# A7_FUNCTION2.net
KiCad netlist of a schematic drawn in Altium Designer
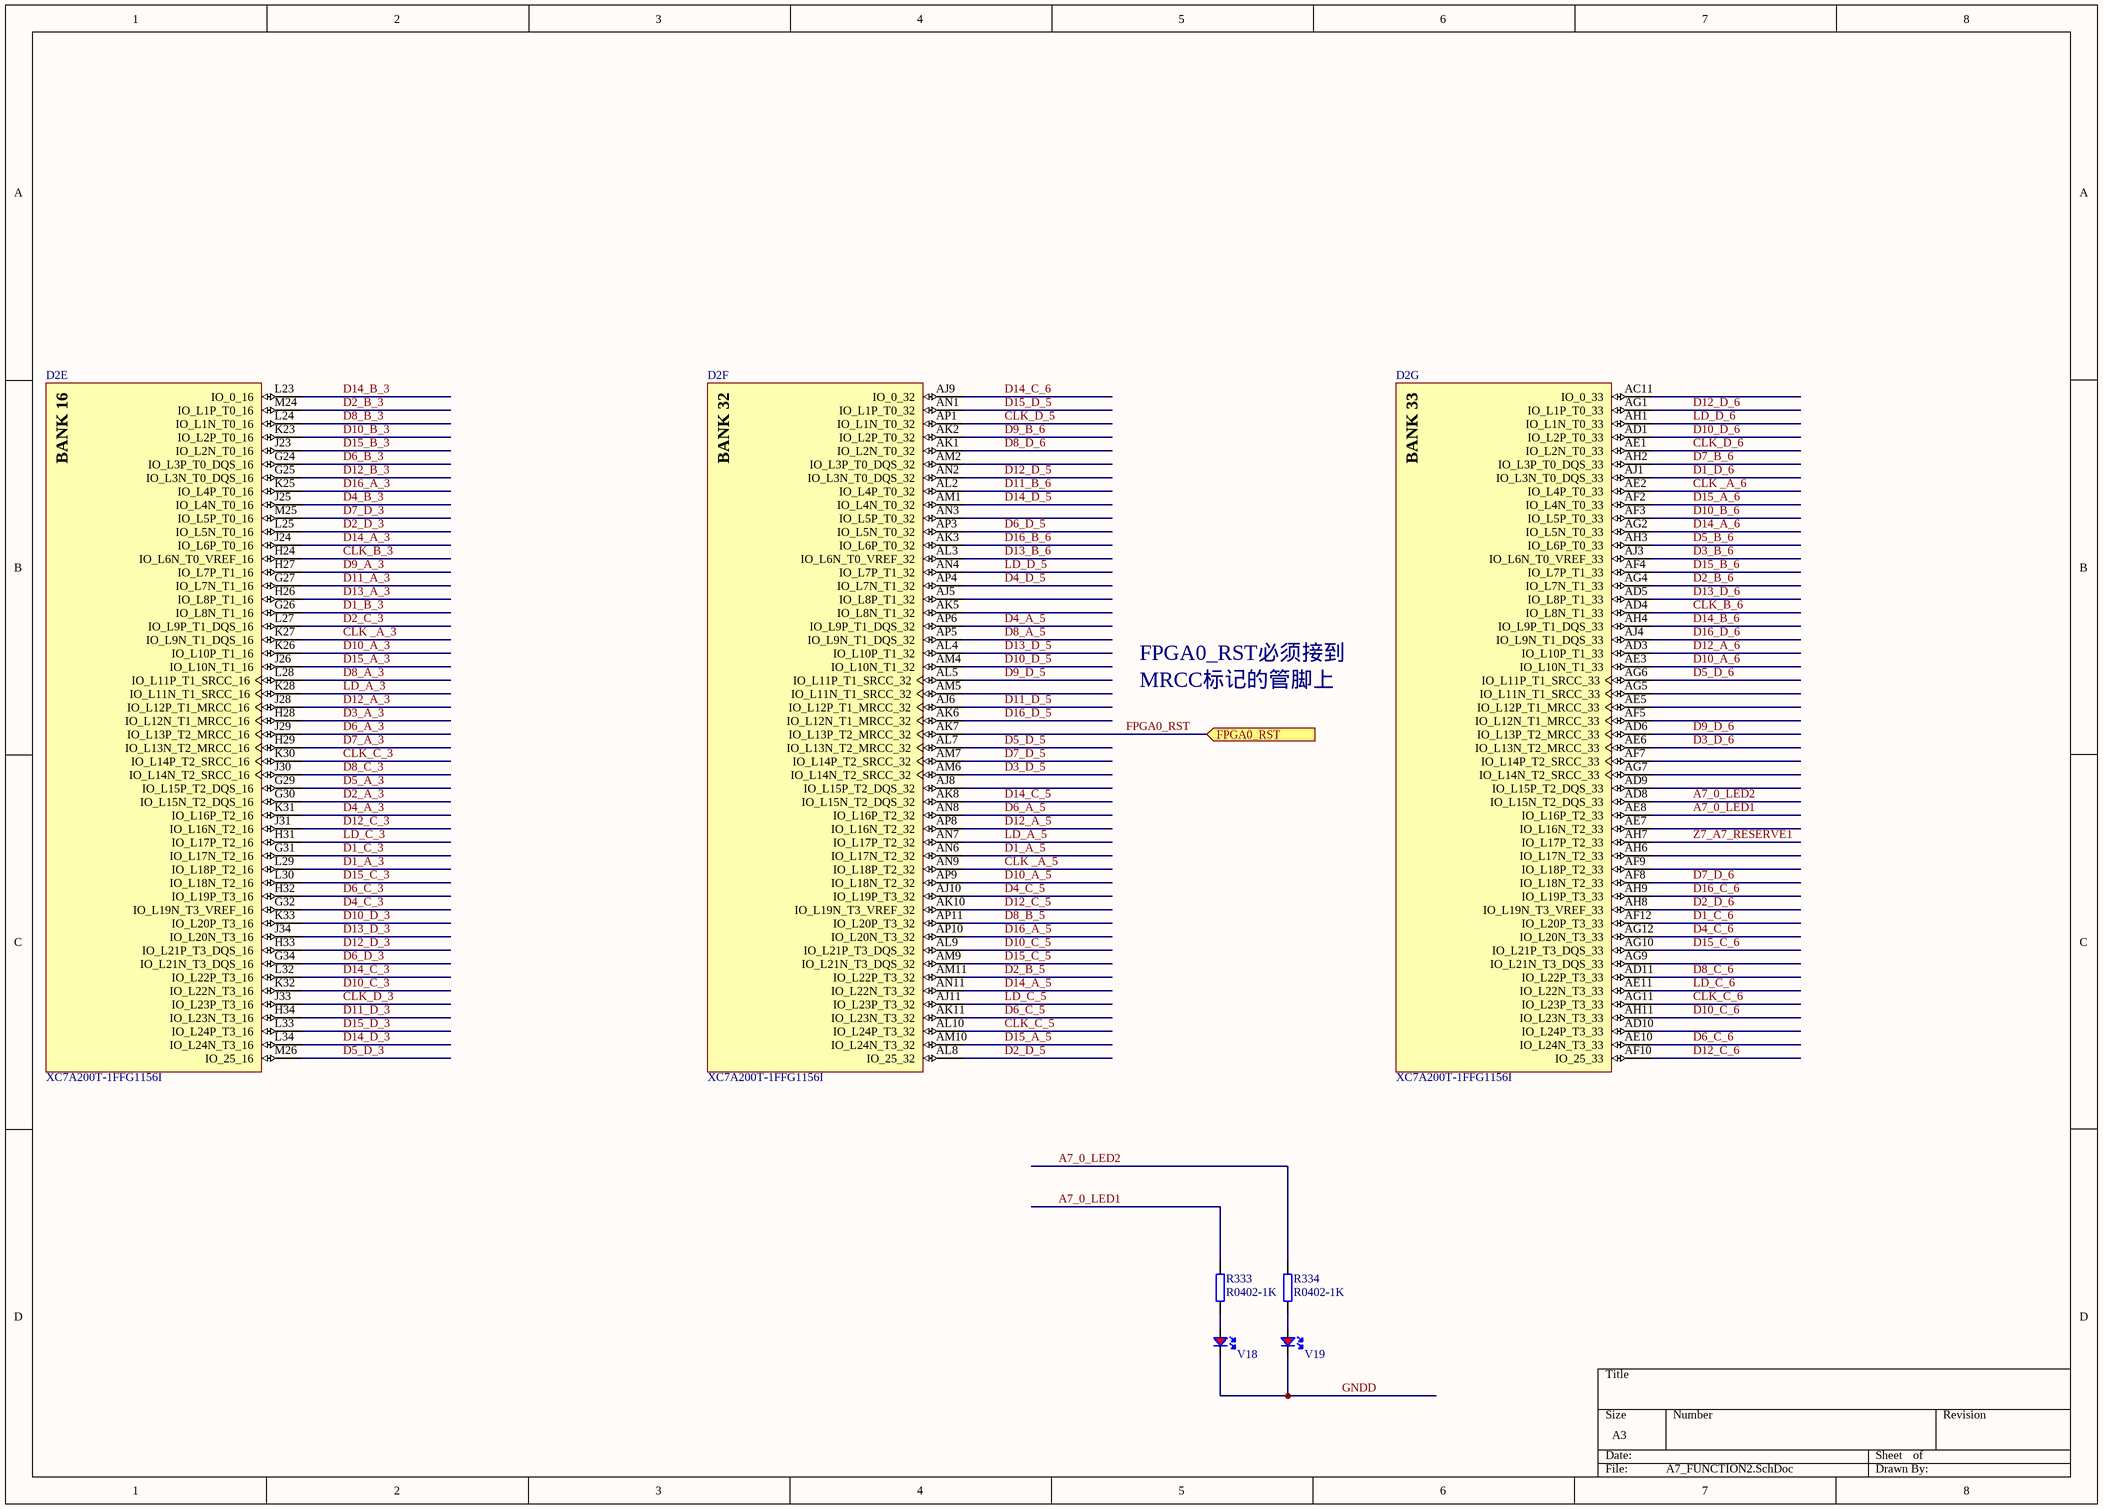
[diagram p0: A7_FUNCTION2.SchDoc]

(export (version "E")
  (design (tool "Eeschema 10.0.6"))
  (components
    (comp (ref "D2")
      (value "XC7A200T-1FFG1156I")
      (footprint "FFG1156")
      (description "Artix-7 FPGA, 500 User I/Os, 16 GTP, 1156-Ball BGA, Speed Grade 1, Industrial Grade, Pb-Free")
      (fields (field (name "GENERIC PART NUMBER") "XC7A200T") (field (name "MANUFACTURER") "Xilinx"))
      (libsource (lib "Xilinx Artix-7") (part "XC7A200T-1FFG1156I"))
    )
    (comp (ref "R333")
      (value "R0402-1K")
      (footprint "R0402")
      (fields (field (name "SCHEMATIC_PART") "RES") (field (name "MANUFACTURER") "SAMSUNG"))
      (libsource (lib "Database_Libs1") (part "RES"))
    )
    (comp (ref "R334")
      (value "R0402-1K")
      (footprint "R0402")
      (fields (field (name "SCHEMATIC_PART") "RES") (field (name "MANUFACTURER") "SAMSUNG"))
      (libsource (lib "Database_Libs1") (part "RES"))
    )
    (comp (ref "V18")
      (value "LED-R0603")
      (footprint "LED-R0603")
      (description "表贴发光二极管, 0603封装, 体积1.6x0.8mm, 红色, 高度0.8mm")
      (fields (field (name "SCHEMATIC_PART") "LED-R"))
      (libsource (lib "Database_Libs1") (part "LED-R"))
    )
    (comp (ref "V19")
      (value "LED-R0603")
      (footprint "LED-R0603")
      (description "表贴发光二极管, 0603封装, 体积1.6x0.8mm, 红色, 高度0.8mm")
      (fields (field (name "SCHEMATIC_PART") "LED-R"))
      (libsource (lib "Database_Libs1") (part "LED-R"))
    )
  )
  (nets
    (net (code "1") (name "/A7_0_LED1") (class "Default")
      (node (ref "D2") (pin "AE8") (pinfunction "IO_L16P_T2_33_AE8") (pintype "bidirectional"))
      (node (ref "R333") (pin "2") (pintype "passive"))
    )
    (net (code "2") (name "/A7_0_LED2") (class "Default")
      (node (ref "D2") (pin "AD8") (pinfunction "IO_L15N_T2_DQS_33_AD8") (pintype "bidirectional"))
      (node (ref "R334") (pin "2") (pintype "passive"))
    )
    (net (code "3") (name "/CLK _A_3") (class "Default")
      (node (ref "D2") (pin "K27") (pinfunction "IO_L9N_T1_DQS_16_K27") (pintype "bidirectional"))
    )
    (net (code "4") (name "/CLK _A_5") (class "Default")
      (node (ref "D2") (pin "AN9") (pinfunction "IO_L18P_T2_32_AN9") (pintype "bidirectional"))
    )
    (net (code "5") (name "/CLK _A_6") (class "Default")
      (node (ref "D2") (pin "AE2") (pinfunction "IO_L4P_T0_33_AE2") (pintype "bidirectional"))
    )
    (net (code "6") (name "/CLK_B_3") (class "Default")
      (node (ref "D2") (pin "H24") (pinfunction "IO_L6N_T0_VREF_16_H24") (pintype "bidirectional"))
    )
    (net (code "7") (name "/CLK_B_6") (class "Default")
      (node (ref "D2") (pin "AD4") (pinfunction "IO_L8N_T1_33_AD4") (pintype "bidirectional"))
    )
    (net (code "8") (name "/CLK_C_3") (class "Default")
      (node (ref "D2") (pin "K30") (pinfunction "IO_L14P_T2_SRCC_16_K30") (pintype "bidirectional"))
    )
    (net (code "9") (name "/CLK_C_5") (class "Default")
      (node (ref "D2") (pin "AL10") (pinfunction "IO_L24P_T3_32_AL10") (pintype "bidirectional"))
    )
    (net (code "10") (name "/CLK_C_6") (class "Default")
      (node (ref "D2") (pin "AG11") (pinfunction "IO_L23P_T3_33_AG11") (pintype "bidirectional"))
    )
    (net (code "11") (name "/CLK_D_3") (class "Default")
      (node (ref "D2") (pin "J33") (pinfunction "IO_L23P_T3_16_J33") (pintype "bidirectional"))
    )
    (net (code "12") (name "/CLK_D_5") (class "Default")
      (node (ref "D2") (pin "AP1") (pinfunction "IO_L1N_T0_32_AP1") (pintype "bidirectional"))
    )
    (net (code "13") (name "/CLK_D_6") (class "Default")
      (node (ref "D2") (pin "AE1") (pinfunction "IO_L2N_T0_33_AE1") (pintype "bidirectional"))
    )
    (net (code "14") (name "/D1_A_3") (class "Default")
      (node (ref "D2") (pin "L29") (pinfunction "IO_L18P_T2_16_L29") (pintype "bidirectional"))
    )
    (net (code "15") (name "/D1_A_5") (class "Default")
      (node (ref "D2") (pin "AN6") (pinfunction "IO_L17N_T2_32_AN6") (pintype "bidirectional"))
    )
    (net (code "16") (name "/D1_B_3") (class "Default")
      (node (ref "D2") (pin "G26") (pinfunction "IO_L8N_T1_16_G26") (pintype "bidirectional"))
    )
    (net (code "17") (name "/D1_C_3") (class "Default")
      (node (ref "D2") (pin "G31") (pinfunction "IO_L17N_T2_16_G31") (pintype "bidirectional"))
    )
    (net (code "18") (name "/D1_C_6") (class "Default")
      (node (ref "D2") (pin "AF12") (pinfunction "IO_L20P_T3_33_AF12") (pintype "bidirectional"))
    )
    (net (code "19") (name "/D1_D_6") (class "Default")
      (node (ref "D2") (pin "AJ1") (pinfunction "IO_L3N_T0_DQS_33_AJ1") (pintype "bidirectional"))
    )
    (net (code "20") (name "/D2_A_3") (class "Default")
      (node (ref "D2") (pin "G30") (pinfunction "IO_L15N_T2_DQS_16_G30") (pintype "bidirectional"))
    )
    (net (code "21") (name "/D2_B_3") (class "Default")
      (node (ref "D2") (pin "M24") (pinfunction "IO_L1P_T0_16_M24") (pintype "bidirectional"))
    )
    (net (code "22") (name "/D2_B_5") (class "Default")
      (node (ref "D2") (pin "AM11") (pinfunction "IO_L22P_T3_32_AM11") (pintype "bidirectional"))
    )
    (net (code "23") (name "/D2_B_6") (class "Default")
      (node (ref "D2") (pin "AG4") (pinfunction "IO_L7N_T1_33_AG4") (pintype "bidirectional"))
    )
    (net (code "24") (name "/D2_C_3") (class "Default")
      (node (ref "D2") (pin "L27") (pinfunction "IO_L9P_T1_DQS_16_L27") (pintype "bidirectional"))
    )
    (net (code "25") (name "/D2_D_3") (class "Default")
      (node (ref "D2") (pin "L25") (pinfunction "IO_L5N_T0_16_L25") (pintype "bidirectional"))
    )
    (net (code "26") (name "/D2_D_5") (class "Default")
      (node (ref "D2") (pin "AL8") (pinfunction "IO_25_32_AL8") (pintype "bidirectional"))
    )
    (net (code "27") (name "/D2_D_6") (class "Default")
      (node (ref "D2") (pin "AH8") (pinfunction "IO_L19N_T3_VREF_33_AH8") (pintype "bidirectional"))
    )
    (net (code "28") (name "/D3_A_3") (class "Default")
      (node (ref "D2") (pin "H28") (pinfunction "IO_L12N_T1_MRCC_16_H28") (pintype "bidirectional"))
    )
    (net (code "29") (name "/D3_B_6") (class "Default")
      (node (ref "D2") (pin "AJ3") (pinfunction "IO_L6N_T0_VREF_33_AJ3") (pintype "bidirectional"))
    )
    (net (code "30") (name "/D3_D_5") (class "Default")
      (node (ref "D2") (pin "AM6") (pinfunction "IO_L14N_T2_SRCC_32_AM6") (pintype "bidirectional"))
    )
    (net (code "31") (name "/D3_D_6") (class "Default")
      (node (ref "D2") (pin "AE6") (pinfunction "IO_L13N_T2_MRCC_33_AE6") (pintype "bidirectional"))
    )
    (net (code "32") (name "/D4_A_3") (class "Default")
      (node (ref "D2") (pin "K31") (pinfunction "IO_L16P_T2_16_K31") (pintype "bidirectional"))
    )
    (net (code "33") (name "/D4_A_5") (class "Default")
      (node (ref "D2") (pin "AP6") (pinfunction "IO_L9P_T1_DQS_32_AP6") (pintype "bidirectional"))
    )
    (net (code "34") (name "/D4_B_3") (class "Default")
      (node (ref "D2") (pin "J25") (pinfunction "IO_L4N_T0_16_J25") (pintype "bidirectional"))
    )
    (net (code "35") (name "/D4_C_3") (class "Default")
      (node (ref "D2") (pin "G32") (pinfunction "IO_L19N_T3_VREF_16_G32") (pintype "bidirectional"))
    )
    (net (code "36") (name "/D4_C_5") (class "Default")
      (node (ref "D2") (pin "AJ10") (pinfunction "IO_L19P_T3_32_AJ10") (pintype "bidirectional"))
    )
    (net (code "37") (name "/D4_C_6") (class "Default")
      (node (ref "D2") (pin "AG12") (pinfunction "IO_L20N_T3_33_AG12") (pintype "bidirectional"))
    )
    (net (code "38") (name "/D4_D_5") (class "Default")
      (node (ref "D2") (pin "AP4") (pinfunction "IO_L7N_T1_32_AP4") (pintype "bidirectional"))
    )
    (net (code "39") (name "/D5_A_3") (class "Default")
      (node (ref "D2") (pin "G29") (pinfunction "IO_L15P_T2_DQS_16_G29") (pintype "bidirectional"))
    )
    (net (code "40") (name "/D5_B_6") (class "Default")
      (node (ref "D2") (pin "AH3") (pinfunction "IO_L6P_T0_33_AH3") (pintype "bidirectional"))
    )
    (net (code "41") (name "/D5_D_3") (class "Default")
      (node (ref "D2") (pin "M26") (pinfunction "IO_25_16_M26") (pintype "bidirectional"))
    )
    (net (code "42") (name "/D5_D_5") (class "Default")
      (node (ref "D2") (pin "AL7") (pinfunction "IO_L13N_T2_MRCC_32_AL7") (pintype "bidirectional"))
    )
    (net (code "43") (name "/D5_D_6") (class "Default")
      (node (ref "D2") (pin "AG6") (pinfunction "IO_L11P_T1_SRCC_33_AG6") (pintype "bidirectional"))
    )
    (net (code "44") (name "/D6_A_3") (class "Default")
      (node (ref "D2") (pin "J29") (pinfunction "IO_L13P_T2_MRCC_16_J29") (pintype "bidirectional"))
    )
    (net (code "45") (name "/D6_A_5") (class "Default")
      (node (ref "D2") (pin "AN8") (pinfunction "IO_L16P_T2_32_AN8") (pintype "bidirectional"))
    )
    (net (code "46") (name "/D6_B_3") (class "Default")
      (node (ref "D2") (pin "G24") (pinfunction "IO_L3P_T0_DQS_16_G24") (pintype "bidirectional"))
    )
    (net (code "47") (name "/D6_C_3") (class "Default")
      (node (ref "D2") (pin "H32") (pinfunction "IO_L19P_T3_16_H32") (pintype "bidirectional"))
    )
    (net (code "48") (name "/D6_C_5") (class "Default")
      (node (ref "D2") (pin "AK11") (pinfunction "IO_L23N_T3_32_AK11") (pintype "bidirectional"))
    )
    (net (code "49") (name "/D6_C_6") (class "Default")
      (node (ref "D2") (pin "AE10") (pinfunction "IO_L24N_T3_33_AE10") (pintype "bidirectional"))
    )
    (net (code "50") (name "/D6_D_3") (class "Default")
      (node (ref "D2") (pin "G34") (pinfunction "IO_L21N_T3_DQS_16_G34") (pintype "bidirectional"))
    )
    (net (code "51") (name "/D6_D_5") (class "Default")
      (node (ref "D2") (pin "AP3") (pinfunction "IO_L5N_T0_32_AP3") (pintype "bidirectional"))
    )
    (net (code "52") (name "/D7_A_3") (class "Default")
      (node (ref "D2") (pin "H29") (pinfunction "IO_L13N_T2_MRCC_16_H29") (pintype "bidirectional"))
    )
    (net (code "53") (name "/D7_B_6") (class "Default")
      (node (ref "D2") (pin "AH2") (pinfunction "IO_L3P_T0_DQS_33_AH2") (pintype "bidirectional"))
    )
    (net (code "54") (name "/D7_D_3") (class "Default")
      (node (ref "D2") (pin "M25") (pinfunction "IO_L5P_T0_16_M25") (pintype "bidirectional"))
    )
    (net (code "55") (name "/D7_D_5") (class "Default")
      (node (ref "D2") (pin "AM7") (pinfunction "IO_L14P_T2_SRCC_32_AM7") (pintype "bidirectional"))
    )
    (net (code "56") (name "/D7_D_6") (class "Default")
      (node (ref "D2") (pin "AF8") (pinfunction "IO_L18N_T2_33_AF8") (pintype "bidirectional"))
    )
    (net (code "57") (name "/D8_A_3") (class "Default")
      (node (ref "D2") (pin "L28") (pinfunction "IO_L11P_T1_SRCC_16_L28") (pintype "bidirectional"))
    )
    (net (code "58") (name "/D8_A_5") (class "Default")
      (node (ref "D2") (pin "AP5") (pinfunction "IO_L9N_T1_DQS_32_AP5") (pintype "bidirectional"))
    )
    (net (code "59") (name "/D8_B_3") (class "Default")
      (node (ref "D2") (pin "L24") (pinfunction "IO_L1N_T0_16_L24") (pintype "bidirectional"))
    )
    (net (code "60") (name "/D8_B_5") (class "Default")
      (node (ref "D2") (pin "AP11") (pinfunction "IO_L20P_T3_32_AP11") (pintype "bidirectional"))
    )
    (net (code "61") (name "/D8_C_3") (class "Default")
      (node (ref "D2") (pin "J30") (pinfunction "IO_L14N_T2_SRCC_16_J30") (pintype "bidirectional"))
    )
    (net (code "62") (name "/D8_C_6") (class "Default")
      (node (ref "D2") (pin "AD11") (pinfunction "IO_L22P_T3_33_AD11") (pintype "bidirectional"))
    )
    (net (code "63") (name "/D8_D_6") (class "Default")
      (node (ref "D2") (pin "AK1") (pinfunction "IO_L2N_T0_32_AK1") (pintype "bidirectional"))
    )
    (net (code "64") (name "/D9_A_3") (class "Default")
      (node (ref "D2") (pin "H27") (pinfunction "IO_L7P_T1_16_H27") (pintype "bidirectional"))
    )
    (net (code "65") (name "/D9_B_6") (class "Default")
      (node (ref "D2") (pin "AK2") (pinfunction "IO_L2P_T0_32_AK2") (pintype "bidirectional"))
    )
    (net (code "66") (name "/D9_D_5") (class "Default")
      (node (ref "D2") (pin "AL5") (pinfunction "IO_L11P_T1_SRCC_32_AL5") (pintype "bidirectional"))
    )
    (net (code "67") (name "/D9_D_6") (class "Default")
      (node (ref "D2") (pin "AD6") (pinfunction "IO_L13P_T2_MRCC_33_AD6") (pintype "bidirectional"))
    )
    (net (code "68") (name "/D10_A_3") (class "Default")
      (node (ref "D2") (pin "K26") (pinfunction "IO_L10P_T1_16_K26") (pintype "bidirectional"))
    )
    (net (code "69") (name "/D10_A_5") (class "Default")
      (node (ref "D2") (pin "AP9") (pinfunction "IO_L18N_T2_32_AP9") (pintype "bidirectional"))
    )
    (net (code "70") (name "/D10_A_6") (class "Default")
      (node (ref "D2") (pin "AE3") (pinfunction "IO_L10N_T1_33_AE3") (pintype "bidirectional"))
    )
    (net (code "71") (name "/D10_B_3") (class "Default")
      (node (ref "D2") (pin "K23") (pinfunction "IO_L2P_T0_16_K23") (pintype "bidirectional"))
    )
    (net (code "72") (name "/D10_B_6") (class "Default")
      (node (ref "D2") (pin "AF3") (pinfunction "IO_L5P_T0_33_AF3") (pintype "bidirectional"))
    )
    (net (code "73") (name "/D10_C_3") (class "Default")
      (node (ref "D2") (pin "K32") (pinfunction "IO_L22N_T3_16_K32") (pintype "bidirectional"))
    )
    (net (code "74") (name "/D10_C_5") (class "Default")
      (node (ref "D2") (pin "AL9") (pinfunction "IO_L21P_T3_DQS_32_AL9") (pintype "bidirectional"))
    )
    (net (code "75") (name "/D10_C_6") (class "Default")
      (node (ref "D2") (pin "AH11") (pinfunction "IO_L23N_T3_33_AH11") (pintype "bidirectional"))
    )
    (net (code "76") (name "/D10_D_3") (class "Default")
      (node (ref "D2") (pin "K33") (pinfunction "IO_L20P_T3_16_K33") (pintype "bidirectional"))
    )
    (net (code "77") (name "/D10_D_5") (class "Default")
      (node (ref "D2") (pin "AM4") (pinfunction "IO_L10N_T1_32_AM4") (pintype "bidirectional"))
    )
    (net (code "78") (name "/D10_D_6") (class "Default")
      (node (ref "D2") (pin "AD1") (pinfunction "IO_L2P_T0_33_AD1") (pintype "bidirectional"))
    )
    (net (code "79") (name "/D11_A_3") (class "Default")
      (node (ref "D2") (pin "G27") (pinfunction "IO_L7N_T1_16_G27") (pintype "bidirectional"))
    )
    (net (code "80") (name "/D11_B_6") (class "Default")
      (node (ref "D2") (pin "AL2") (pinfunction "IO_L4P_T0_32_AL2") (pintype "bidirectional"))
    )
    (net (code "81") (name "/D11_D_3") (class "Default")
      (node (ref "D2") (pin "H34") (pinfunction "IO_L23N_T3_16_H34") (pintype "bidirectional"))
    )
    (net (code "82") (name "/D11_D_5") (class "Default")
      (node (ref "D2") (pin "AJ6") (pinfunction "IO_L12P_T1_MRCC_32_AJ6") (pintype "bidirectional"))
    )
    (net (code "83") (name "/D12_A_3") (class "Default")
      (node (ref "D2") (pin "J28") (pinfunction "IO_L12P_T1_MRCC_16_J28") (pintype "bidirectional"))
    )
    (net (code "84") (name "/D12_A_5") (class "Default")
      (node (ref "D2") (pin "AP8") (pinfunction "IO_L16N_T2_32_AP8") (pintype "bidirectional"))
    )
    (net (code "85") (name "/D12_A_6") (class "Default")
      (node (ref "D2") (pin "AD3") (pinfunction "IO_L10P_T1_33_AD3") (pintype "bidirectional"))
    )
    (net (code "86") (name "/D12_B_3") (class "Default")
      (node (ref "D2") (pin "G25") (pinfunction "IO_L3N_T0_DQS_16_G25") (pintype "bidirectional"))
    )
    (net (code "87") (name "/D12_C_3") (class "Default")
      (node (ref "D2") (pin "J31") (pinfunction "IO_L16N_T2_16_J31") (pintype "bidirectional"))
    )
    (net (code "88") (name "/D12_C_5") (class "Default")
      (node (ref "D2") (pin "AK10") (pinfunction "IO_L19N_T3_VREF_32_AK10") (pintype "bidirectional"))
    )
    (net (code "89") (name "/D12_C_6") (class "Default")
      (node (ref "D2") (pin "AF10") (pinfunction "IO_25_33_AF10") (pintype "bidirectional"))
    )
    (net (code "90") (name "/D12_D_3") (class "Default")
      (node (ref "D2") (pin "H33") (pinfunction "IO_L21P_T3_DQS_16_H33") (pintype "bidirectional"))
    )
    (net (code "91") (name "/D12_D_5") (class "Default")
      (node (ref "D2") (pin "AN2") (pinfunction "IO_L3N_T0_DQS_32_AN2") (pintype "bidirectional"))
    )
    (net (code "92") (name "/D12_D_6") (class "Default")
      (node (ref "D2") (pin "AG1") (pinfunction "IO_L1P_T0_33_AG1") (pintype "bidirectional"))
    )
    (net (code "93") (name "/D13_A_3") (class "Default")
      (node (ref "D2") (pin "H26") (pinfunction "IO_L8P_T1_16_H26") (pintype "bidirectional"))
    )
    (net (code "94") (name "/D13_B_6") (class "Default")
      (node (ref "D2") (pin "AL3") (pinfunction "IO_L6N_T0_VREF_32_AL3") (pintype "bidirectional"))
    )
    (net (code "95") (name "/D13_D_3") (class "Default")
      (node (ref "D2") (pin "J34") (pinfunction "IO_L20N_T3_16_J34") (pintype "bidirectional"))
    )
    (net (code "96") (name "/D13_D_5") (class "Default")
      (node (ref "D2") (pin "AL4") (pinfunction "IO_L10P_T1_32_AL4") (pintype "bidirectional"))
    )
    (net (code "97") (name "/D13_D_6") (class "Default")
      (node (ref "D2") (pin "AD5") (pinfunction "IO_L8P_T1_33_AD5") (pintype "bidirectional"))
    )
    (net (code "98") (name "/D14_A_3") (class "Default")
      (node (ref "D2") (pin "J24") (pinfunction "IO_L6P_T0_16_J24") (pintype "bidirectional"))
    )
    (net (code "99") (name "/D14_A_5") (class "Default")
      (node (ref "D2") (pin "AN11") (pinfunction "IO_L22N_T3_32_AN11") (pintype "bidirectional"))
    )
    (net (code "100") (name "/D14_A_6") (class "Default")
      (node (ref "D2") (pin "AG2") (pinfunction "IO_L5N_T0_33_AG2") (pintype "bidirectional"))
    )
    (net (code "101") (name "/D14_B_3") (class "Default")
      (node (ref "D2") (pin "L23") (pinfunction "IO_0_16_L23") (pintype "bidirectional"))
    )
    (net (code "102") (name "/D14_B_6") (class "Default")
      (node (ref "D2") (pin "AH4") (pinfunction "IO_L9P_T1_DQS_33_AH4") (pintype "bidirectional"))
    )
    (net (code "103") (name "/D14_C_3") (class "Default")
      (node (ref "D2") (pin "L32") (pinfunction "IO_L22P_T3_16_L32") (pintype "bidirectional"))
    )
    (net (code "104") (name "/D14_C_5") (class "Default")
      (node (ref "D2") (pin "AK8") (pinfunction "IO_L15N_T2_DQS_32_AK8") (pintype "bidirectional"))
    )
    (net (code "105") (name "/D14_C_6") (class "Default")
      (node (ref "D2") (pin "AJ9") (pinfunction "IO_0_32_AJ9") (pintype "bidirectional"))
    )
    (net (code "106") (name "/D14_D_3") (class "Default")
      (node (ref "D2") (pin "L34") (pinfunction "IO_L24N_T3_16_L34") (pintype "bidirectional"))
    )
    (net (code "107") (name "/D14_D_5") (class "Default")
      (node (ref "D2") (pin "AM1") (pinfunction "IO_L4N_T0_32_AM1") (pintype "bidirectional"))
    )
    (net (code "108") (name "/D15_A_3") (class "Default")
      (node (ref "D2") (pin "J26") (pinfunction "IO_L10N_T1_16_J26") (pintype "bidirectional"))
    )
    (net (code "109") (name "/D15_A_5") (class "Default")
      (node (ref "D2") (pin "AM10") (pinfunction "IO_L24N_T3_32_AM10") (pintype "bidirectional"))
    )
    (net (code "110") (name "/D15_A_6") (class "Default")
      (node (ref "D2") (pin "AF2") (pinfunction "IO_L4N_T0_33_AF2") (pintype "bidirectional"))
    )
    (net (code "111") (name "/D15_B_3") (class "Default")
      (node (ref "D2") (pin "J23") (pinfunction "IO_L2N_T0_16_J23") (pintype "bidirectional"))
    )
    (net (code "112") (name "/D15_B_6") (class "Default")
      (node (ref "D2") (pin "AF4") (pinfunction "IO_L7P_T1_33_AF4") (pintype "bidirectional"))
    )
    (net (code "113") (name "/D15_C_3") (class "Default")
      (node (ref "D2") (pin "L30") (pinfunction "IO_L18N_T2_16_L30") (pintype "bidirectional"))
    )
    (net (code "114") (name "/D15_C_5") (class "Default")
      (node (ref "D2") (pin "AM9") (pinfunction "IO_L21N_T3_DQS_32_AM9") (pintype "bidirectional"))
    )
    (net (code "115") (name "/D15_C_6") (class "Default")
      (node (ref "D2") (pin "AG10") (pinfunction "IO_L21P_T3_DQS_33_AG10") (pintype "bidirectional"))
    )
    (net (code "116") (name "/D15_D_3") (class "Default")
      (node (ref "D2") (pin "L33") (pinfunction "IO_L24P_T3_16_L33") (pintype "bidirectional"))
    )
    (net (code "117") (name "/D15_D_5") (class "Default")
      (node (ref "D2") (pin "AN1") (pinfunction "IO_L1P_T0_32_AN1") (pintype "bidirectional"))
    )
    (net (code "118") (name "/D16_A_3") (class "Default")
      (node (ref "D2") (pin "K25") (pinfunction "IO_L4P_T0_16_K25") (pintype "bidirectional"))
    )
    (net (code "119") (name "/D16_A_5") (class "Default")
      (node (ref "D2") (pin "AP10") (pinfunction "IO_L20N_T3_32_AP10") (pintype "bidirectional"))
    )
    (net (code "120") (name "/D16_B_6") (class "Default")
      (node (ref "D2") (pin "AK3") (pinfunction "IO_L6P_T0_32_AK3") (pintype "bidirectional"))
    )
    (net (code "121") (name "/D16_C_6") (class "Default")
      (node (ref "D2") (pin "AH9") (pinfunction "IO_L19P_T3_33_AH9") (pintype "bidirectional"))
    )
    (net (code "122") (name "/D16_D_5") (class "Default")
      (node (ref "D2") (pin "AK6") (pinfunction "IO_L12N_T1_MRCC_32_AK6") (pintype "bidirectional"))
    )
    (net (code "123") (name "/D16_D_6") (class "Default")
      (node (ref "D2") (pin "AJ4") (pinfunction "IO_L9N_T1_DQS_33_AJ4") (pintype "bidirectional"))
    )
    (net (code "124") (name "/FPGA0_RST") (class "Default")
      (node (ref "D2") (pin "AK7") (pinfunction "IO_L13P_T2_MRCC_32_AK7") (pintype "bidirectional"))
    )
    (net (code "125") (name "/GNDD") (class "Default")
      (node (ref "V18") (pin "2") (pinfunction "K_2") (pintype "passive"))
      (node (ref "V19") (pin "2") (pinfunction "K_2") (pintype "passive"))
    )
    (net (code "126") (name "/LD_A_3") (class "Default")
      (node (ref "D2") (pin "K28") (pinfunction "IO_L11N_T1_SRCC_16_K28") (pintype "bidirectional"))
    )
    (net (code "127") (name "/LD_A_5") (class "Default")
      (node (ref "D2") (pin "AN7") (pinfunction "IO_L17P_T2_32_AN7") (pintype "bidirectional"))
    )
    (net (code "128") (name "/LD_C_3") (class "Default")
      (node (ref "D2") (pin "H31") (pinfunction "IO_L17P_T2_16_H31") (pintype "bidirectional"))
    )
    (net (code "129") (name "/LD_C_5") (class "Default")
      (node (ref "D2") (pin "AJ11") (pinfunction "IO_L23P_T3_32_AJ11") (pintype "bidirectional"))
    )
    (net (code "130") (name "/LD_C_6") (class "Default")
      (node (ref "D2") (pin "AE11") (pinfunction "IO_L22N_T3_33_AE11") (pintype "bidirectional"))
    )
    (net (code "131") (name "/LD_D_5") (class "Default")
      (node (ref "D2") (pin "AN4") (pinfunction "IO_L7P_T1_32_AN4") (pintype "bidirectional"))
    )
    (net (code "132") (name "/LD_D_6") (class "Default")
      (node (ref "D2") (pin "AH1") (pinfunction "IO_L1N_T0_33_AH1") (pintype "bidirectional"))
    )
    (net (code "133") (name "/Z7_A7_RESERVE1") (class "Default")
      (node (ref "D2") (pin "AH7") (pinfunction "IO_L17P_T2_33_AH7") (pintype "bidirectional"))
    )
    (net (code "134") (name "Net-(V18-A)") (class "Default")
      (node (ref "R333") (pin "1") (pintype "passive"))
      (node (ref "V18") (pin "1") (pinfunction "A_1") (pintype "passive"))
    )
    (net (code "135") (name "Net-(V19-A)") (class "Default")
      (node (ref "R334") (pin "1") (pintype "passive"))
      (node (ref "V19") (pin "1") (pinfunction "A_1") (pintype "passive"))
    )
    (net (code "136") (name "unconnected-(D2F-IO_L3P_T0_DQS_32-PadAM2)") (class "Default")
      (node (ref "D2") (pin "AM2") (pinfunction "IO_L3P_T0_DQS_32_AM2") (pintype "bidirectional"))
    )
    (net (code "137") (name "unconnected-(D2F-IO_L5P_T0_32-PadAN3)") (class "Default")
      (node (ref "D2") (pin "AN3") (pinfunction "IO_L5P_T0_32_AN3") (pintype "bidirectional"))
    )
    (net (code "138") (name "unconnected-(D2F-IO_L8N_T1_32-PadAK5)") (class "Default")
      (node (ref "D2") (pin "AK5") (pinfunction "IO_L8N_T1_32_AK5") (pintype "bidirectional"))
    )
    (net (code "139") (name "unconnected-(D2F-IO_L8P_T1_32-PadAJ5)") (class "Default")
      (node (ref "D2") (pin "AJ5") (pinfunction "IO_L8P_T1_32_AJ5") (pintype "bidirectional"))
    )
    (net (code "140") (name "unconnected-(D2F-IO_L11N_T1_SRCC_32-PadAM5)") (class "Default")
      (node (ref "D2") (pin "AM5") (pinfunction "IO_L11N_T1_SRCC_32_AM5") (pintype "bidirectional"))
    )
    (net (code "141") (name "unconnected-(D2F-IO_L15P_T2_DQS_32-PadAJ8)") (class "Default")
      (node (ref "D2") (pin "AJ8") (pinfunction "IO_L15P_T2_DQS_32_AJ8") (pintype "bidirectional"))
    )
    (net (code "142") (name "unconnected-(D2G-IO_0_33-PadAC11)") (class "Default")
      (node (ref "D2") (pin "AC11") (pinfunction "IO_0_33_AC11") (pintype "bidirectional"))
    )
    (net (code "143") (name "unconnected-(D2G-IO_L11N_T1_SRCC_33-PadAG5)") (class "Default")
      (node (ref "D2") (pin "AG5") (pinfunction "IO_L11N_T1_SRCC_33_AG5") (pintype "bidirectional"))
    )
    (net (code "144") (name "unconnected-(D2G-IO_L12N_T1_MRCC_33-PadAF5)") (class "Default")
      (node (ref "D2") (pin "AF5") (pinfunction "IO_L12N_T1_MRCC_33_AF5") (pintype "bidirectional"))
    )
    (net (code "145") (name "unconnected-(D2G-IO_L12P_T1_MRCC_33-PadAE5)") (class "Default")
      (node (ref "D2") (pin "AE5") (pinfunction "IO_L12P_T1_MRCC_33_AE5") (pintype "bidirectional"))
    )
    (net (code "146") (name "unconnected-(D2G-IO_L14N_T2_SRCC_33-PadAG7)") (class "Default")
      (node (ref "D2") (pin "AG7") (pinfunction "IO_L14N_T2_SRCC_33_AG7") (pintype "bidirectional"))
    )
    (net (code "147") (name "unconnected-(D2G-IO_L14P_T2_SRCC_33-PadAF7)") (class "Default")
      (node (ref "D2") (pin "AF7") (pinfunction "IO_L14P_T2_SRCC_33_AF7") (pintype "bidirectional"))
    )
    (net (code "148") (name "unconnected-(D2G-IO_L15P_T2_DQS_33-PadAD9)") (class "Default")
      (node (ref "D2") (pin "AD9") (pinfunction "IO_L15P_T2_DQS_33_AD9") (pintype "bidirectional"))
    )
    (net (code "149") (name "unconnected-(D2G-IO_L16N_T2_33-PadAE7)") (class "Default")
      (node (ref "D2") (pin "AE7") (pinfunction "IO_L16N_T2_33_AE7") (pintype "bidirectional"))
    )
    (net (code "150") (name "unconnected-(D2G-IO_L17N_T2_33-PadAH6)") (class "Default")
      (node (ref "D2") (pin "AH6") (pinfunction "IO_L17N_T2_33_AH6") (pintype "bidirectional"))
    )
    (net (code "151") (name "unconnected-(D2G-IO_L18P_T2_33-PadAF9)") (class "Default")
      (node (ref "D2") (pin "AF9") (pinfunction "IO_L18P_T2_33_AF9") (pintype "bidirectional"))
    )
    (net (code "152") (name "unconnected-(D2G-IO_L21N_T3_DQS_33-PadAG9)") (class "Default")
      (node (ref "D2") (pin "AG9") (pinfunction "IO_L21N_T3_DQS_33_AG9") (pintype "bidirectional"))
    )
    (net (code "153") (name "unconnected-(D2G-IO_L24P_T3_33-PadAD10)") (class "Default")
      (node (ref "D2") (pin "AD10") (pinfunction "IO_L24P_T3_33_AD10") (pintype "bidirectional"))
    )
  )
)
